# DIGITAL.net
KiCad netlist of a schematic drawn in Altium Designer
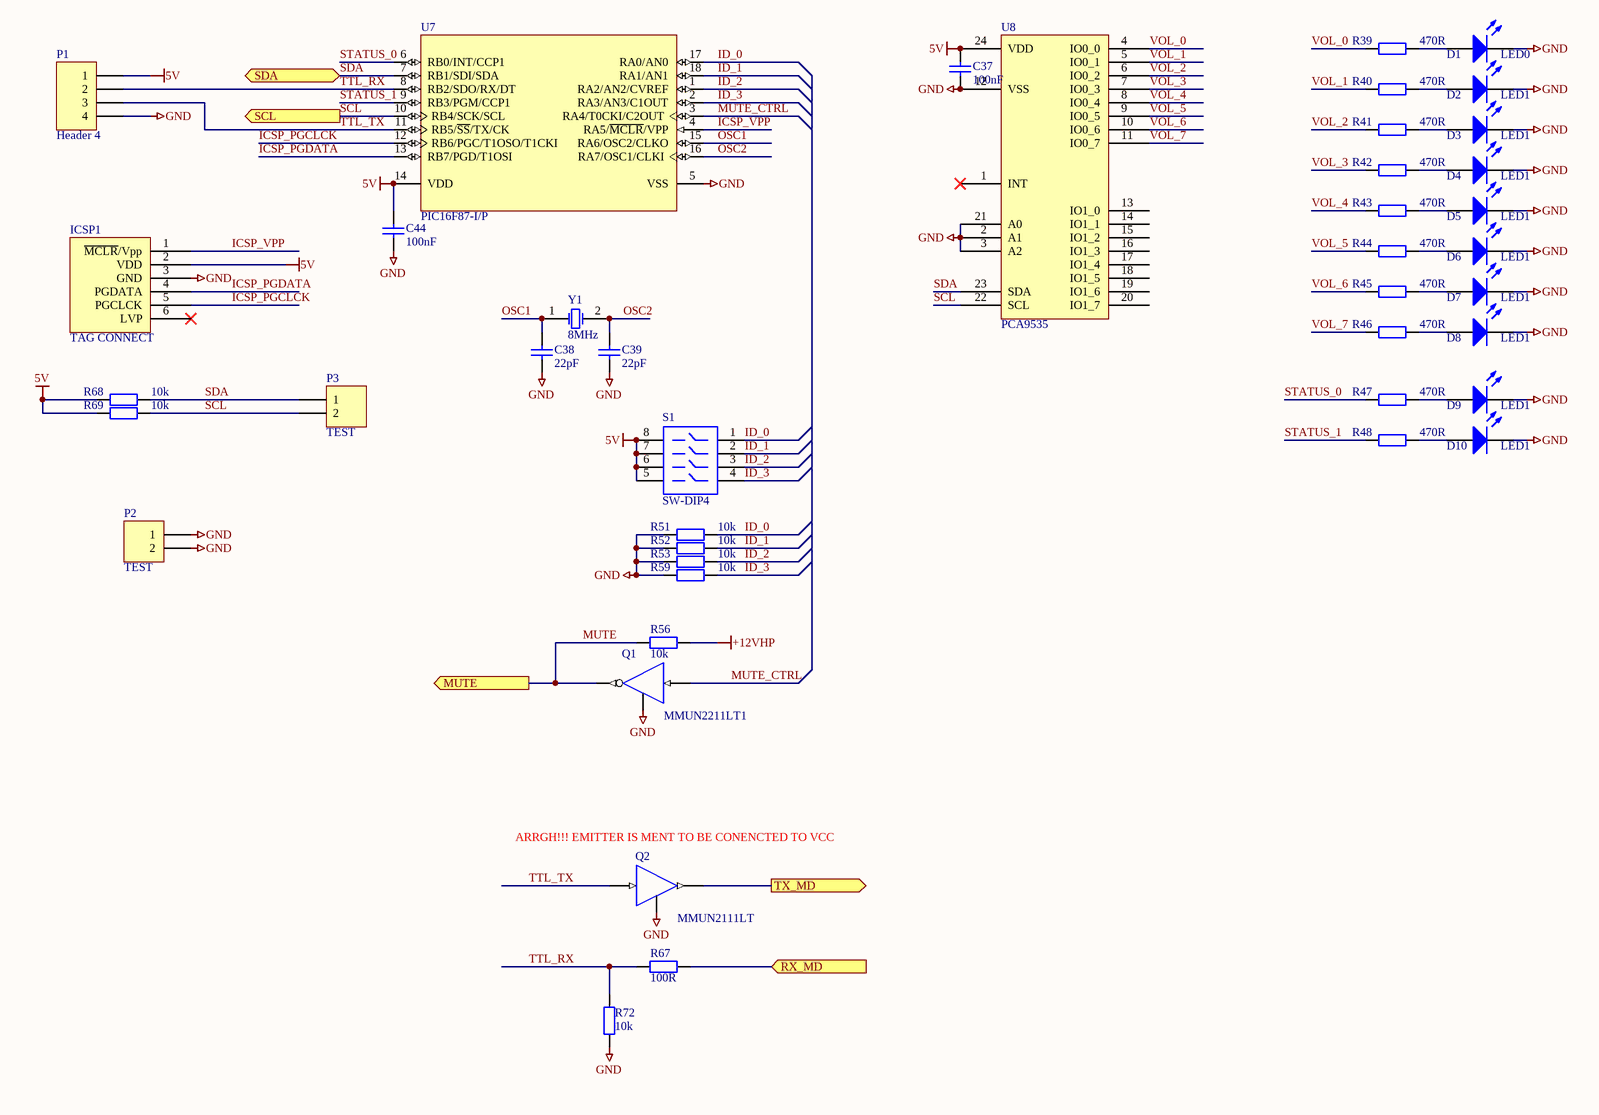
[diagram p0: DIGITAL.SchDoc]

(export (version "E")
  (design (tool "Eeschema 10.0.6"))
  (components
    (comp (ref "C37")
      (value "100nF")
      (footprint "CAP (3D) - 0603")
      (description "Capacitor")
      (fields
        (field (name "MANUFACTURER") "YAEGO")
        (field (name "MANUFACTURER PART NO.") "CC0603ZRY5V9BB104")
      )
      (libsource (lib "Miscellaneous Devices") (part "Cap"))
    )
    (comp (ref "C38")
      (value "22pF")
      (footprint "CAP (3D) - 0603")
      (description "Capacitor")
      (fields
        (field (name "MANUFACTURER") "XICON")
        (field (name "MANUFACTURER PART NO.") "140-CC504N220J-RC")
      )
      (libsource (lib "Miscellaneous Devices") (part "Cap"))
    )
    (comp (ref "C39")
      (value "22pF")
      (footprint "CAP (3D) - 0603")
      (description "Capacitor")
      (fields
        (field (name "MANUFACTURER") "XICON")
        (field (name "MANUFACTURER PART NO.") "140-CC504N220J-RC")
      )
      (libsource (lib "Miscellaneous Devices") (part "Cap"))
    )
    (comp (ref "C44")
      (value "100nF")
      (footprint "CAP (3D) - 0603")
      (description "Capacitor")
      (fields
        (field (name "MANUFACTURER") "YAEGO")
        (field (name "MANUFACTURER PART NO.") "CC0603ZRY5V9BB104")
      )
      (libsource (lib "Miscellaneous Devices") (part "Cap"))
    )
    (comp (ref "D1")
      (value "LED0")
      (footprint "LED 3MM")
      (description "Typical INFRARED GaAs LED")
      (fields (field (name "MANUFACTURER") "VISHAY") (field (name "MANUFACTURER PART NO.") "TLUR4401"))
      (libsource (lib "Miscellaneous Devices") (part "LED0"))
    )
    (comp (ref "D2")
      (value "LED1")
      (footprint "LED 3MM")
      (description "Typical RED GaAs LED")
      (fields (field (name "MANUFACTURER") "VISHAY") (field (name "MANUFACTURER PART NO.") "TLHE4600"))
      (libsource (lib "Miscellaneous Devices") (part "LED1"))
    )
    (comp (ref "D3")
      (value "LED1")
      (footprint "LED 3MM")
      (description "Typical RED GaAs LED")
      (fields (field (name "MANUFACTURER") "VISHAY") (field (name "MANUFACTURER PART NO.") "TLHG4405"))
      (libsource (lib "Miscellaneous Devices") (part "LED1"))
    )
    (comp (ref "D4")
      (value "LED1")
      (footprint "LED 3MM")
      (description "Typical RED GaAs LED")
      (fields (field (name "MANUFACTURER") "VISHAY") (field (name "MANUFACTURER PART NO.") "TLHG4405"))
      (libsource (lib "Miscellaneous Devices") (part "LED1"))
    )
    (comp (ref "D5")
      (value "LED1")
      (footprint "LED 3MM")
      (description "Typical RED GaAs LED")
      (fields (field (name "MANUFACTURER") "VISHAY") (field (name "MANUFACTURER PART NO.") "TLHG4405"))
      (libsource (lib "Miscellaneous Devices") (part "LED1"))
    )
    (comp (ref "D6")
      (value "LED1")
      (footprint "LED 3MM")
      (description "Typical RED GaAs LED")
      (fields (field (name "MANUFACTURER") "VISHAY") (field (name "MANUFACTURER PART NO.") "TLHG4405"))
      (libsource (lib "Miscellaneous Devices") (part "LED1"))
    )
    (comp (ref "D7")
      (value "LED1")
      (footprint "LED 3MM")
      (description "Typical RED GaAs LED")
      (fields (field (name "MANUFACTURER") "VISHAY") (field (name "MANUFACTURER PART NO.") "TLHG4405"))
      (libsource (lib "Miscellaneous Devices") (part "LED1"))
    )
    (comp (ref "D8")
      (value "LED1")
      (footprint "LED 3MM")
      (description "Typical RED GaAs LED")
      (fields (field (name "MANUFACTURER") "VISHAY") (field (name "MANUFACTURER PART NO.") "TLHG4405"))
      (libsource (lib "Miscellaneous Devices") (part "LED1"))
    )
    (comp (ref "D9")
      (value "LED1")
      (footprint "LED 3MM")
      (description "Typical RED GaAs LED")
      (fields (field (name "MANUFACTURER") "VISHAY") (field (name "MANUFACTURER PART NO.") "TLHB4400"))
      (libsource (lib "Miscellaneous Devices") (part "LED1"))
    )
    (comp (ref "D10")
      (value "LED1")
      (footprint "LED 3MM")
      (description "Typical RED GaAs LED")
      (fields (field (name "MANUFACTURER") "VISHAY") (field (name "MANUFACTURER PART NO.") "TLHB4400"))
      (libsource (lib "Miscellaneous Devices") (part "LED1"))
    )
    (comp (ref "ICSP1")
      (value "TAG CONNECT")
      (footprint "ICSP - TAG CONNECT TYPE2")
      (fields (field (name "MANUFACTURER") "N/A - PCB ARTWORK"))
      (libsource (lib "I2C PENDANT") (part "ICSP - TAG CONNECT"))
    )
    (comp (ref "P1")
      (value "Header 4")
      (footprint "HDR1X4")
      (description "Header, 4-Pin")
      (fields (field (name "MANUFACTURER") "NA PCB ARTWORK"))
      (libsource (lib "Miscellaneous Connectors") (part "Header 4"))
    )
    (comp (ref "P2")
      (value "TEST")
      (footprint "HDR1X2")
      (description "Header, 2-Pin")
      (fields (field (name "MANUFACTURER") "NA PCB ARTWORK"))
      (libsource (lib "Miscellaneous Connectors") (part "Header 2"))
    )
    (comp (ref "P3")
      (value "TEST")
      (footprint "HDR1X2")
      (description "Header, 2-Pin")
      (fields (field (name "MANUFACTURER") "NA PCB ARTWORK"))
      (libsource (lib "") (part "Header 2_1"))
    )
    (comp (ref "Q1")
      (value "MMUN2211LT1")
      (footprint "SOT23-3L")
      (fields
        (field (name "MOUSER PART NO.") "863-MMUN2211LT1G")
        (field (name "MANUFACTURER") "ON SEMO")
        (field (name "MANUFACTURER PART NO.") "MMUN2211LT1G")
      )
      (libsource (lib "401 CCPA") (part "NPN DIGITAL TRANSISTOR"))
    )
    (comp (ref "Q2")
      (value "MMUN2111LT")
      (footprint "SOT23-3L")
      (description "MMUN2111LT1")
      (fields (field (name "MOUSER PART NO.") "863-MMUN2111LT1G") (field (name "MANUFACTURER") "ON SEMI"))
      (libsource (lib "Distribution Amp_1") (part "PNP DIGITAL TRANSISTOR"))
    )
    (comp (ref "R39")
      (value "470R")
      (footprint "RES (3D) - 0603")
      (description "Resistor")
      (fields (field (name "MANUFACTURER") "YAEGO") (field (name "MANUFACTURER PART NO.") "AC0603FR-07470RL"))
      (libsource (lib "Miscellaneous Devices") (part "Res2"))
    )
    (comp (ref "R40")
      (value "470R")
      (footprint "RES (3D) - 0603")
      (description "Resistor")
      (fields (field (name "MANUFACTURER") "YAEGO") (field (name "MANUFACTURER PART NO.") "AC0603FR-07470RL"))
      (libsource (lib "Miscellaneous Devices") (part "Res2"))
    )
    (comp (ref "R41")
      (value "470R")
      (footprint "RES (3D) - 0603")
      (description "Resistor")
      (fields (field (name "MANUFACTURER") "YAEGO") (field (name "MANUFACTURER PART NO.") "AC0603FR-07470RL"))
      (libsource (lib "Miscellaneous Devices") (part "Res2"))
    )
    (comp (ref "R42")
      (value "470R")
      (footprint "RES (3D) - 0603")
      (description "Resistor")
      (fields (field (name "MANUFACTURER") "YAEGO") (field (name "MANUFACTURER PART NO.") "AC0603FR-07470RL"))
      (libsource (lib "Miscellaneous Devices") (part "Res2"))
    )
    (comp (ref "R43")
      (value "470R")
      (footprint "RES (3D) - 0603")
      (description "Resistor")
      (fields (field (name "MANUFACTURER") "YAEGO") (field (name "MANUFACTURER PART NO.") "AC0603FR-07470RL"))
      (libsource (lib "Miscellaneous Devices") (part "Res2"))
    )
    (comp (ref "R44")
      (value "470R")
      (footprint "RES (3D) - 0603")
      (description "Resistor")
      (fields (field (name "MANUFACTURER") "YAEGO") (field (name "MANUFACTURER PART NO.") "AC0603FR-07470RL"))
      (libsource (lib "Miscellaneous Devices") (part "Res2"))
    )
    (comp (ref "R45")
      (value "470R")
      (footprint "RES (3D) - 0603")
      (description "Resistor")
      (fields (field (name "MANUFACTURER") "YAEGO") (field (name "MANUFACTURER PART NO.") "AC0603FR-07470RL"))
      (libsource (lib "Miscellaneous Devices") (part "Res2"))
    )
    (comp (ref "R46")
      (value "470R")
      (footprint "RES (3D) - 0603")
      (description "Resistor")
      (fields (field (name "MANUFACTURER") "YAEGO") (field (name "MANUFACTURER PART NO.") "AC0603FR-07470RL"))
      (libsource (lib "Miscellaneous Devices") (part "Res2"))
    )
    (comp (ref "R47")
      (value "470R")
      (footprint "RES (3D) - 0603")
      (description "Resistor")
      (fields (field (name "MANUFACTURER") "YAEGO") (field (name "MANUFACTURER PART NO.") "AC0603FR-07470RL"))
      (libsource (lib "Miscellaneous Devices") (part "Res2"))
    )
    (comp (ref "R48")
      (value "470R")
      (footprint "RES (3D) - 0603")
      (description "Resistor")
      (fields (field (name "MANUFACTURER") "YAEGO") (field (name "MANUFACTURER PART NO.") "AC0603FR-07470RL"))
      (libsource (lib "Miscellaneous Devices") (part "Res2"))
    )
    (comp (ref "R51")
      (value "10k")
      (footprint "RES (3D) - 0603")
      (description "Resistor")
      (fields (field (name "MANUFACTURER") "YAEGO") (field (name "MANUFACTURER PART NO.") "AC0603JR-0710KL"))
      (libsource (lib "Miscellaneous Devices") (part "Res2"))
    )
    (comp (ref "R52")
      (value "10k")
      (footprint "RES (3D) - 0603")
      (description "Resistor")
      (fields (field (name "MANUFACTURER") "YAEGO") (field (name "MANUFACTURER PART NO.") "AC0603JR-0710KL"))
      (libsource (lib "Miscellaneous Devices") (part "Res2"))
    )
    (comp (ref "R53")
      (value "10k")
      (footprint "RES (3D) - 0603")
      (description "Resistor")
      (fields (field (name "MANUFACTURER") "YAEGO") (field (name "MANUFACTURER PART NO.") "AC0603JR-0710KL"))
      (libsource (lib "Miscellaneous Devices") (part "Res2"))
    )
    (comp (ref "R56")
      (value "10k")
      (footprint "RES (3D) - 0603")
      (description "Resistor")
      (fields (field (name "MANUFACTURER") "YAEGO") (field (name "MANUFACTURER PART NO.") "AC0603JR-0710KL"))
      (libsource (lib "") (part "Res2_1"))
    )
    (comp (ref "R59")
      (value "10k")
      (footprint "RES (3D) - 0603")
      (description "Resistor")
      (fields (field (name "MANUFACTURER") "YAEGO") (field (name "MANUFACTURER PART NO.") "AC0603JR-0710KL"))
      (libsource (lib "Miscellaneous Devices") (part "Res2"))
    )
    (comp (ref "R67")
      (value "100R")
      (footprint "RES (3D) - 0603")
      (description "Resistor")
      (fields (field (name "MANUFACTURER") "YAEGO") (field (name "MANUFACTURER PART NO.") "RC0603FR-07100RL"))
      (libsource (lib "Miscellaneous Devices") (part "Res2"))
    )
    (comp (ref "R68")
      (value "10k")
      (footprint "RES (3D) - 0603")
      (description "Resistor")
      (fields (field (name "MANUFACTURER") "YAEGO") (field (name "MANUFACTURER PART NO.") "AC0603JR-0710KL"))
      (libsource (lib "Miscellaneous Devices") (part "Res2"))
    )
    (comp (ref "R69")
      (value "10k")
      (footprint "RES (3D) - 0603")
      (description "Resistor")
      (fields (field (name "MANUFACTURER") "YAEGO") (field (name "MANUFACTURER PART NO.") "AC0603JR-0710KL"))
      (libsource (lib "Miscellaneous Devices") (part "Res2"))
    )
    (comp (ref "R72")
      (value "10k")
      (footprint "RES (3D) - 0603")
      (description "Resistor")
      (fields (field (name "MANUFACTURER") "YAEGO") (field (name "MANUFACTURER PART NO.") "AC0603JR-0710KL"))
      (libsource (lib "") (part "Res2_2"))
    )
    (comp (ref "S1")
      (value "SW-DIP4")
      (footprint "DIP-8")
      (description "DIP Switch")
      (fields (field (name "MANUFACTURER") "NA PCB ARTWORK"))
      (libsource (lib "Miscellaneous Devices") (part "SW-DIP4"))
    )
    (comp (ref "U7")
      (value "PIC16F87-I/P")
      (footprint "PDIP300-18")
      (fields (field (name "MANUFACTURER") "MICROCHIP") (field (name "MOUSER PART NO.") "579-PIC16F87-I/P"))
      (libsource (lib "Microchip Microcontroller 8-Bit PIC16F") (part "PIC16F87-I/P"))
    )
    (comp (ref "U8")
      (value "PCA9535")
      (footprint "WSO24_L")
      (description "PCA9535 I2C BUS 16 BIT IO EXPANDER")
      (fields
        (field (name "MANUFACTURER") "NXP Semiconductors")
        (field (name "MANUFACTURER PART NO.") "PCA9535D,112")
      )
      (libsource (lib "NASCO") (part "PCA9535"))
    )
    (comp (ref "Y1")
      (value "8MHz")
      (footprint "HC-49U")
      (description "Crystal Oscillator")
      (fields
        (field (name "MANUFACTURER") "CTS Electronic Components")
        (field (name "MANUFACTURER PART NO.") "ATS080B")
      )
      (libsource (lib "Miscellaneous Devices") (part "XTAL"))
    )
  )
  (nets
    (net (code "1") (name "+12VHP") (class "Default")
      (node (ref "R56") (pin "1") (pinfunction "1_1") (pintype "passive"))
    )
    (net (code "2") (name "/ICSP_PGCLCK") (class "Default")
      (node (ref "ICSP1") (pin "5") (pinfunction "PGCLCK_5") (pintype "passive"))
      (node (ref "U7") (pin "12") (pinfunction "RB6/PGC/T1OSO/T1CKI_12") (pintype "bidirectional"))
    )
    (net (code "3") (name "/ICSP_PGDATA") (class "Default")
      (node (ref "ICSP1") (pin "4") (pinfunction "PGDATA_4") (pintype "passive"))
      (node (ref "U7") (pin "13") (pinfunction "RB7/PGD/T1OSI_13") (pintype "bidirectional"))
    )
    (net (code "4") (name "/ICSP_VPP") (class "Default")
      (node (ref "ICSP1") (pin "1") (pinfunction "~{MCLR}/Vpp_1") (pintype "passive"))
      (node (ref "U7") (pin "4") (pinfunction "RA5/~{MCLR}/VPP_4") (pintype "input"))
    )
    (net (code "5") (name "/ID_0") (class "Default")
      (node (ref "R51") (pin "2") (pinfunction "2_2") (pintype "passive"))
      (node (ref "S1") (pin "1") (pinfunction "1_1") (pintype "passive"))
      (node (ref "U7") (pin "17") (pinfunction "RA0/AN0_17") (pintype "bidirectional"))
    )
    (net (code "6") (name "/ID_1") (class "Default")
      (node (ref "R52") (pin "2") (pinfunction "2_2") (pintype "passive"))
      (node (ref "S1") (pin "2") (pinfunction "2_2") (pintype "passive"))
      (node (ref "U7") (pin "18") (pinfunction "RA1/AN1_18") (pintype "bidirectional"))
    )
    (net (code "7") (name "/ID_2") (class "Default")
      (node (ref "R53") (pin "2") (pinfunction "2_2") (pintype "passive"))
      (node (ref "S1") (pin "3") (pinfunction "3_3") (pintype "passive"))
      (node (ref "U7") (pin "1") (pinfunction "RA2/AN2/CVREF_1") (pintype "bidirectional"))
    )
    (net (code "8") (name "/ID_3") (class "Default")
      (node (ref "R59") (pin "2") (pinfunction "2_2") (pintype "passive"))
      (node (ref "S1") (pin "4") (pinfunction "4_4") (pintype "passive"))
      (node (ref "U7") (pin "2") (pinfunction "RA3/AN3/C1OUT_2") (pintype "bidirectional"))
    )
    (net (code "9") (name "/MUTE") (class "Default")
      (node (ref "Q1") (pin "3") (pinfunction "C_3") (pintype "output"))
      (node (ref "R56") (pin "2") (pinfunction "2_2") (pintype "passive"))
    )
    (net (code "10") (name "/MUTE_CTRL") (class "Default")
      (node (ref "Q1") (pin "1") (pinfunction "B_1") (pintype "input"))
      (node (ref "U7") (pin "3") (pinfunction "RA4/T0CKI/C2OUT_3") (pintype "bidirectional"))
    )
    (net (code "11") (name "/OSC1") (class "Default")
      (node (ref "C38") (pin "2") (pinfunction "2_2") (pintype "passive"))
      (node (ref "U7") (pin "15") (pinfunction "RA6/OSC2/CLKO_15") (pintype "bidirectional"))
      (node (ref "Y1") (pin "1") (pinfunction "OSC1_1") (pintype "passive"))
    )
    (net (code "12") (name "/OSC2") (class "Default")
      (node (ref "C39") (pin "2") (pinfunction "2_2") (pintype "passive"))
      (node (ref "U7") (pin "16") (pinfunction "RA7/OSC1/CLKI_16") (pintype "bidirectional"))
      (node (ref "Y1") (pin "2") (pinfunction "OSC2_2") (pintype "passive"))
    )
    (net (code "13") (name "/RX_MD") (class "Default")
      (node (ref "R67") (pin "2") (pinfunction "2_2") (pintype "passive"))
    )
    (net (code "14") (name "/SCL") (class "Default")
      (node (ref "P3") (pin "2") (pinfunction "2_2") (pintype "passive"))
      (node (ref "R69") (pin "2") (pinfunction "2_2") (pintype "passive"))
      (node (ref "U7") (pin "10") (pinfunction "RB4/SCK/SCL_10") (pintype "bidirectional"))
      (node (ref "U8") (pin "22") (pinfunction "SCL_22") (pintype "passive"))
    )
    (net (code "15") (name "/SDA") (class "Default")
      (node (ref "P3") (pin "1") (pinfunction "1_1") (pintype "passive"))
      (node (ref "R68") (pin "2") (pinfunction "2_2") (pintype "passive"))
      (node (ref "U7") (pin "7") (pinfunction "RB1/SDI/SDA_7") (pintype "bidirectional"))
      (node (ref "U8") (pin "23") (pinfunction "SDA_23") (pintype "passive"))
    )
    (net (code "16") (name "/STATUS_0") (class "Default")
      (node (ref "R47") (pin "1") (pinfunction "1_1") (pintype "passive"))
      (node (ref "U7") (pin "6") (pinfunction "RB0/INT/CCP1_6") (pintype "bidirectional"))
    )
    (net (code "17") (name "/STATUS_1") (class "Default")
      (node (ref "R48") (pin "1") (pinfunction "1_1") (pintype "passive"))
      (node (ref "U7") (pin "9") (pinfunction "RB3/PGM/CCP1_9") (pintype "bidirectional"))
    )
    (net (code "18") (name "/TTL_RX") (class "Default")
      (node (ref "P1") (pin "2") (pinfunction "2_2") (pintype "passive"))
      (node (ref "R67") (pin "1") (pinfunction "1_1") (pintype "passive"))
      (node (ref "R72") (pin "2") (pinfunction "2_2") (pintype "passive"))
      (node (ref "U7") (pin "8") (pinfunction "RB2/SDO/RX/DT_8") (pintype "bidirectional"))
    )
    (net (code "19") (name "/TTL_TX") (class "Default")
      (node (ref "P1") (pin "3") (pinfunction "3_3") (pintype "passive"))
      (node (ref "Q2") (pin "1") (pinfunction "B_1") (pintype "input"))
      (node (ref "U7") (pin "11") (pinfunction "RB5/~{SS}/TX/CK_11") (pintype "bidirectional"))
    )
    (net (code "20") (name "/TX_MD") (class "Default")
      (node (ref "Q2") (pin "3") (pinfunction "C_3") (pintype "output"))
    )
    (net (code "21") (name "/VOL_0") (class "Default")
      (node (ref "R39") (pin "1") (pinfunction "1_1") (pintype "passive"))
      (node (ref "U8") (pin "4") (pinfunction "IO0_0_4") (pintype "passive"))
    )
    (net (code "22") (name "/VOL_1") (class "Default")
      (node (ref "R40") (pin "1") (pinfunction "1_1") (pintype "passive"))
      (node (ref "U8") (pin "5") (pinfunction "IO0_1_5") (pintype "passive"))
    )
    (net (code "23") (name "/VOL_2") (class "Default")
      (node (ref "R41") (pin "1") (pinfunction "1_1") (pintype "passive"))
      (node (ref "U8") (pin "6") (pinfunction "IO0_2_6") (pintype "passive"))
    )
    (net (code "24") (name "/VOL_3") (class "Default")
      (node (ref "R42") (pin "1") (pinfunction "1_1") (pintype "passive"))
      (node (ref "U8") (pin "7") (pinfunction "IO0_3_7") (pintype "passive"))
    )
    (net (code "25") (name "/VOL_4") (class "Default")
      (node (ref "R43") (pin "1") (pinfunction "1_1") (pintype "passive"))
      (node (ref "U8") (pin "8") (pinfunction "IO0_4_8") (pintype "passive"))
    )
    (net (code "26") (name "/VOL_5") (class "Default")
      (node (ref "R44") (pin "1") (pinfunction "1_1") (pintype "passive"))
      (node (ref "U8") (pin "9") (pinfunction "IO0_5_9") (pintype "passive"))
    )
    (net (code "27") (name "/VOL_6") (class "Default")
      (node (ref "R45") (pin "1") (pinfunction "1_1") (pintype "passive"))
      (node (ref "U8") (pin "10") (pinfunction "IO0_6_10") (pintype "passive"))
    )
    (net (code "28") (name "/VOL_7") (class "Default")
      (node (ref "R46") (pin "1") (pinfunction "1_1") (pintype "passive"))
      (node (ref "U8") (pin "11") (pinfunction "IO0_7_11") (pintype "passive"))
    )
    (net (code "29") (name "5V") (class "Default")
      (node (ref "C37") (pin "2") (pinfunction "2_2") (pintype "passive"))
      (node (ref "C44") (pin "2") (pinfunction "2_2") (pintype "passive"))
      (node (ref "ICSP1") (pin "2") (pinfunction "VDD_2") (pintype "passive"))
      (node (ref "P1") (pin "1") (pinfunction "1_1") (pintype "passive"))
      (node (ref "R68") (pin "1") (pinfunction "1_1") (pintype "passive"))
      (node (ref "R69") (pin "1") (pinfunction "1_1") (pintype "passive"))
      (node (ref "S1") (pin "5") (pinfunction "5_5") (pintype "passive"))
      (node (ref "S1") (pin "6") (pinfunction "6_6") (pintype "passive"))
      (node (ref "S1") (pin "7") (pinfunction "7_7") (pintype "passive"))
      (node (ref "S1") (pin "8") (pinfunction "8_8") (pintype "passive"))
      (node (ref "U7") (pin "14") (pinfunction "VDD_14") (pintype "power_in"))
      (node (ref "U8") (pin "24") (pinfunction "VDD_24") (pintype "passive"))
    )
    (net (code "30") (name "GND") (class "Default")
      (node (ref "C37") (pin "1") (pinfunction "1_1") (pintype "passive"))
      (node (ref "C38") (pin "1") (pinfunction "1_1") (pintype "passive"))
      (node (ref "C39") (pin "1") (pinfunction "1_1") (pintype "passive"))
      (node (ref "C44") (pin "1") (pinfunction "1_1") (pintype "passive"))
      (node (ref "D1") (pin "2") (pinfunction "K_2") (pintype "passive"))
      (node (ref "D10") (pin "2") (pinfunction "K_2") (pintype "passive"))
      (node (ref "D2") (pin "2") (pinfunction "K_2") (pintype "passive"))
      (node (ref "D3") (pin "2") (pinfunction "K_2") (pintype "passive"))
      (node (ref "D4") (pin "2") (pinfunction "K_2") (pintype "passive"))
      (node (ref "D5") (pin "2") (pinfunction "K_2") (pintype "passive"))
      (node (ref "D6") (pin "2") (pinfunction "K_2") (pintype "passive"))
      (node (ref "D7") (pin "2") (pinfunction "K_2") (pintype "passive"))
      (node (ref "D8") (pin "2") (pinfunction "K_2") (pintype "passive"))
      (node (ref "D9") (pin "2") (pinfunction "K_2") (pintype "passive"))
      (node (ref "ICSP1") (pin "3") (pinfunction "GND_3") (pintype "passive"))
      (node (ref "P1") (pin "4") (pinfunction "4_4") (pintype "passive"))
      (node (ref "P2") (pin "1") (pinfunction "1_1") (pintype "passive"))
      (node (ref "P2") (pin "2") (pinfunction "2_2") (pintype "passive"))
      (node (ref "Q1") (pin "2") (pinfunction "E_2") (pintype "passive"))
      (node (ref "Q2") (pin "2") (pinfunction "E_2") (pintype "passive"))
      (node (ref "R51") (pin "1") (pinfunction "1_1") (pintype "passive"))
      (node (ref "R52") (pin "1") (pinfunction "1_1") (pintype "passive"))
      (node (ref "R53") (pin "1") (pinfunction "1_1") (pintype "passive"))
      (node (ref "R59") (pin "1") (pinfunction "1_1") (pintype "passive"))
      (node (ref "R72") (pin "1") (pinfunction "1_1") (pintype "passive"))
      (node (ref "U7") (pin "5") (pinfunction "VSS_5") (pintype "power_in"))
      (node (ref "U8") (pin "12") (pinfunction "VSS_12") (pintype "passive"))
      (node (ref "U8") (pin "2") (pinfunction "A1_2") (pintype "passive"))
      (node (ref "U8") (pin "21") (pinfunction "A0_21") (pintype "passive"))
      (node (ref "U8") (pin "3") (pinfunction "A2_3") (pintype "passive"))
    )
    (net (code "31") (name "Net-(D1-A)") (class "Default")
      (node (ref "D1") (pin "1") (pinfunction "A_1") (pintype "passive"))
      (node (ref "R39") (pin "2") (pinfunction "2_2") (pintype "passive"))
    )
    (net (code "32") (name "Net-(D2-A)") (class "Default")
      (node (ref "D2") (pin "1") (pinfunction "A_1") (pintype "passive"))
      (node (ref "R40") (pin "2") (pinfunction "2_2") (pintype "passive"))
    )
    (net (code "33") (name "Net-(D3-A)") (class "Default")
      (node (ref "D3") (pin "1") (pinfunction "A_1") (pintype "passive"))
      (node (ref "R41") (pin "2") (pinfunction "2_2") (pintype "passive"))
    )
    (net (code "34") (name "Net-(D4-A)") (class "Default")
      (node (ref "D4") (pin "1") (pinfunction "A_1") (pintype "passive"))
      (node (ref "R42") (pin "2") (pinfunction "2_2") (pintype "passive"))
    )
    (net (code "35") (name "Net-(D5-A)") (class "Default")
      (node (ref "D5") (pin "1") (pinfunction "A_1") (pintype "passive"))
      (node (ref "R43") (pin "2") (pinfunction "2_2") (pintype "passive"))
    )
    (net (code "36") (name "Net-(D6-A)") (class "Default")
      (node (ref "D6") (pin "1") (pinfunction "A_1") (pintype "passive"))
      (node (ref "R44") (pin "2") (pinfunction "2_2") (pintype "passive"))
    )
    (net (code "37") (name "Net-(D7-A)") (class "Default")
      (node (ref "D7") (pin "1") (pinfunction "A_1") (pintype "passive"))
      (node (ref "R45") (pin "2") (pinfunction "2_2") (pintype "passive"))
    )
    (net (code "38") (name "Net-(D8-A)") (class "Default")
      (node (ref "D8") (pin "1") (pinfunction "A_1") (pintype "passive"))
      (node (ref "R46") (pin "2") (pinfunction "2_2") (pintype "passive"))
    )
    (net (code "39") (name "Net-(D9-A)") (class "Default")
      (node (ref "D9") (pin "1") (pinfunction "A_1") (pintype "passive"))
      (node (ref "R47") (pin "2") (pinfunction "2_2") (pintype "passive"))
    )
    (net (code "40") (name "Net-(D10-A)") (class "Default")
      (node (ref "D10") (pin "1") (pinfunction "A_1") (pintype "passive"))
      (node (ref "R48") (pin "2") (pinfunction "2_2") (pintype "passive"))
    )
    (net (code "41") (name "unconnected-(ICSP1-LVP-Pad6)") (class "Default")
      (node (ref "ICSP1") (pin "6") (pinfunction "LVP_6") (pintype "passive+no_connect"))
    )
    (net (code "42") (name "unconnected-(U8-INT-Pad1)") (class "Default")
      (node (ref "U8") (pin "1") (pinfunction "INT_1") (pintype "open_collector+no_connect"))
    )
    (net (code "43") (name "unconnected-(U8-IO1_0-Pad13)") (class "Default")
      (node (ref "U8") (pin "13") (pinfunction "IO1_0_13") (pintype "passive"))
    )
    (net (code "44") (name "unconnected-(U8-IO1_1-Pad14)") (class "Default")
      (node (ref "U8") (pin "14") (pinfunction "IO1_1_14") (pintype "passive"))
    )
    (net (code "45") (name "unconnected-(U8-IO1_2-Pad15)") (class "Default")
      (node (ref "U8") (pin "15") (pinfunction "IO1_2_15") (pintype "passive"))
    )
    (net (code "46") (name "unconnected-(U8-IO1_3-Pad16)") (class "Default")
      (node (ref "U8") (pin "16") (pinfunction "IO1_3_16") (pintype "passive"))
    )
    (net (code "47") (name "unconnected-(U8-IO1_4-Pad17)") (class "Default")
      (node (ref "U8") (pin "17") (pinfunction "IO1_4_17") (pintype "passive"))
    )
    (net (code "48") (name "unconnected-(U8-IO1_5-Pad18)") (class "Default")
      (node (ref "U8") (pin "18") (pinfunction "IO1_5_18") (pintype "passive"))
    )
    (net (code "49") (name "unconnected-(U8-IO1_6-Pad19)") (class "Default")
      (node (ref "U8") (pin "19") (pinfunction "IO1_6_19") (pintype "passive"))
    )
    (net (code "50") (name "unconnected-(U8-IO1_7-Pad20)") (class "Default")
      (node (ref "U8") (pin "20") (pinfunction "IO1_7_20") (pintype "passive"))
    )
  )
)
